# glove5.net
KiCad netlist of a schematic drawn in EAGLE
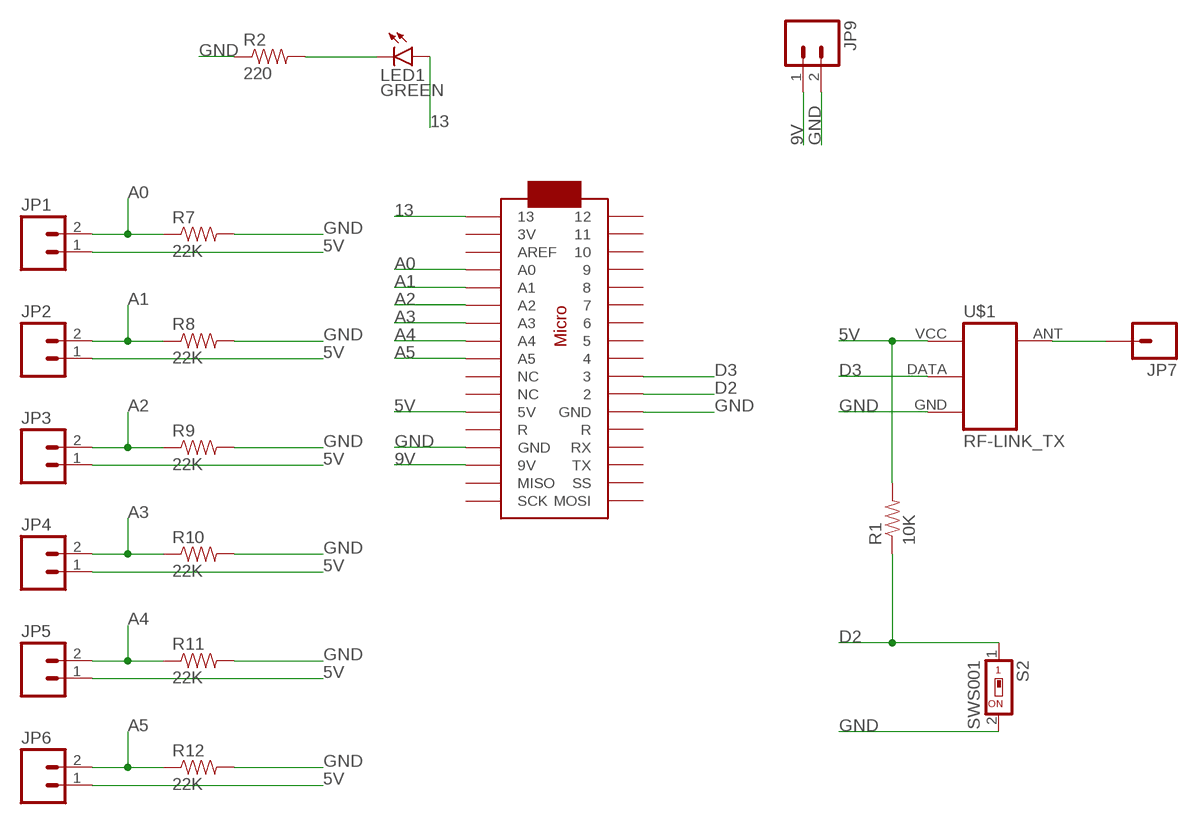
[diagram p0: schematic, sheet 1]

(export (version "E")
  (design (tool "Eeschema 10.0.6"))
  (components
    (comp (ref "JP1")
      (value "M02LOCK_LONGPADS")
      (footprint "eagle-import:1X02_LOCK_LONGPADS")
      (libsource (lib "eagle-import") (part "M02LOCK_LONGPADS"))
    )
    (comp (ref "JP2")
      (value "M02LOCK_LONGPADS")
      (footprint "eagle-import:1X02_LOCK_LONGPADS")
      (libsource (lib "eagle-import") (part "M02LOCK_LONGPADS"))
    )
    (comp (ref "JP3")
      (value "M02LOCK_LONGPADS")
      (footprint "eagle-import:1X02_LOCK_LONGPADS")
      (libsource (lib "eagle-import") (part "M02LOCK_LONGPADS"))
    )
    (comp (ref "JP4")
      (value "M02LOCK_LONGPADS")
      (footprint "eagle-import:1X02_LOCK_LONGPADS")
      (libsource (lib "eagle-import") (part "M02LOCK_LONGPADS"))
    )
    (comp (ref "JP5")
      (value "M02LOCK_LONGPADS")
      (footprint "eagle-import:1X02_LOCK_LONGPADS")
      (libsource (lib "eagle-import") (part "M02LOCK_LONGPADS"))
    )
    (comp (ref "JP6")
      (value "M02LOCK_LONGPADS")
      (footprint "eagle-import:1X02_LOCK_LONGPADS")
      (libsource (lib "eagle-import") (part "M02LOCK_LONGPADS"))
    )
    (comp (ref "JP7")
      (value "M01PTH_LONGPAD")
      (footprint "eagle-import:1X01_LONGPAD")
      (libsource (lib "eagle-import") (part "M01PTH_LONGPAD"))
    )
    (comp (ref "JP9")
      (value "M02LOCK_LONGPADS")
      (footprint "eagle-import:1X02_LOCK_LONGPADS")
      (libsource (lib "eagle-import") (part "M02LOCK_LONGPADS"))
    )
    (comp (ref "LED1")
      (value "GREEN")
      (footprint "eagle-import:FKIT-LED-1206")
      (libsource (lib "eagle-import") (part "LED-FKIT-1206"))
    )
    (comp (ref "R1")
      (value "10K")
      (footprint "eagle-import:1206")
      (libsource (lib "eagle-import") (part "RESISTOR1206"))
    )
    (comp (ref "R2")
      (value "220")
      (footprint "eagle-import:1206")
      (libsource (lib "eagle-import") (part "RESISTOR1206"))
    )
    (comp (ref "R7")
      (value "22K")
      (footprint "eagle-import:1206")
      (libsource (lib "eagle-import") (part "RESISTOR1206"))
    )
    (comp (ref "R8")
      (value "22K")
      (footprint "eagle-import:1206")
      (libsource (lib "eagle-import") (part "RESISTOR1206"))
    )
    (comp (ref "R9")
      (value "22K")
      (footprint "eagle-import:1206")
      (libsource (lib "eagle-import") (part "RESISTOR1206"))
    )
    (comp (ref "R10")
      (value "22K")
      (footprint "eagle-import:1206")
      (libsource (lib "eagle-import") (part "RESISTOR1206"))
    )
    (comp (ref "R11")
      (value "22K")
      (footprint "eagle-import:1206")
      (libsource (lib "eagle-import") (part "RESISTOR1206"))
    )
    (comp (ref "R12")
      (value "22K")
      (footprint "eagle-import:1206")
      (libsource (lib "eagle-import") (part "RESISTOR1206"))
    )
    (comp (ref "S2")
      (value "SWS001")
      (footprint "eagle-import:SMS-001")
      (libsource (lib "eagle-import") (part "SWS001"))
    )
    (comp (ref "U$1")
      (value "RF-LINK_TX")
      (footprint "eagle-import:RF-LINK_TX")
      (libsource (lib "eagle-import") (part "RF-LINK_TX"))
    )
    (comp (ref "U$3")
      (value "ARDUINOMICRO")
      (footprint "eagle-import:ARDUINOMICRO")
      (libsource (lib "eagle-import") (part "ARDUINOMICRO"))
    )
  )
  (nets
    (net (code "1") (name "/5V") (class "Default")
      (node (ref "JP1") (pin "1") (pinfunction "1_1") (pintype "passive"))
      (node (ref "JP2") (pin "1") (pinfunction "1_1") (pintype "passive"))
      (node (ref "JP3") (pin "1") (pinfunction "1_1") (pintype "passive"))
      (node (ref "JP4") (pin "1") (pinfunction "1_1") (pintype "passive"))
      (node (ref "JP5") (pin "1") (pinfunction "1_1") (pintype "passive"))
      (node (ref "JP6") (pin "1") (pinfunction "1_1") (pintype "passive"))
      (node (ref "R1") (pin "2") (pinfunction "2_2") (pintype "passive"))
      (node (ref "U$1") (pin "VCC") (pinfunction "+5V_VCC") (pintype "power_in"))
      (node (ref "U$3") (pin "P$23") (pinfunction "5V_P$23") (pintype "bidirectional"))
    )
    (net (code "2") (name "/9V") (class "Default")
      (node (ref "JP9") (pin "1") (pinfunction "1_1") (pintype "passive"))
      (node (ref "U$3") (pin "P$20") (pinfunction "9V_P$20") (pintype "bidirectional"))
    )
    (net (code "3") (name "/13") (class "Default")
      (node (ref "LED1") (pin "A") (pinfunction "A_A") (pintype "passive"))
      (node (ref "U$3") (pin "P$34") (pinfunction "13_P$34") (pintype "bidirectional"))
    )
    (net (code "4") (name "/A0") (class "Default")
      (node (ref "JP1") (pin "2") (pinfunction "2_2") (pintype "passive"))
      (node (ref "R7") (pin "1") (pinfunction "1_1") (pintype "passive"))
      (node (ref "U$3") (pin "P$31") (pinfunction "A0_P$31") (pintype "bidirectional"))
    )
    (net (code "5") (name "/A1") (class "Default")
      (node (ref "JP2") (pin "2") (pinfunction "2_2") (pintype "passive"))
      (node (ref "R8") (pin "1") (pinfunction "1_1") (pintype "passive"))
      (node (ref "U$3") (pin "P$30") (pinfunction "A1_P$30") (pintype "bidirectional"))
    )
    (net (code "6") (name "/A2") (class "Default")
      (node (ref "JP3") (pin "2") (pinfunction "2_2") (pintype "passive"))
      (node (ref "R9") (pin "1") (pinfunction "1_1") (pintype "passive"))
      (node (ref "U$3") (pin "P$29") (pinfunction "A2_P$29") (pintype "bidirectional"))
    )
    (net (code "7") (name "/A3") (class "Default")
      (node (ref "JP4") (pin "2") (pinfunction "2_2") (pintype "passive"))
      (node (ref "R10") (pin "1") (pinfunction "1_1") (pintype "passive"))
      (node (ref "U$3") (pin "P$28") (pinfunction "A3_P$28") (pintype "bidirectional"))
    )
    (net (code "8") (name "/A4") (class "Default")
      (node (ref "JP5") (pin "2") (pinfunction "2_2") (pintype "passive"))
      (node (ref "R11") (pin "1") (pinfunction "1_1") (pintype "passive"))
      (node (ref "U$3") (pin "P$27") (pinfunction "A4_P$27") (pintype "bidirectional"))
    )
    (net (code "9") (name "/A5") (class "Default")
      (node (ref "JP6") (pin "2") (pinfunction "2_2") (pintype "passive"))
      (node (ref "R12") (pin "1") (pinfunction "1_1") (pintype "passive"))
      (node (ref "U$3") (pin "P$26") (pinfunction "A5_P$26") (pintype "bidirectional"))
    )
    (net (code "10") (name "/D2") (class "Default")
      (node (ref "R1") (pin "1") (pinfunction "1_1") (pintype "passive"))
      (node (ref "S2") (pin "1") (pinfunction "1_1") (pintype "passive"))
      (node (ref "U$3") (pin "P$11") (pinfunction "2_P$11") (pintype "bidirectional"))
    )
    (net (code "11") (name "/D3") (class "Default")
      (node (ref "U$1") (pin "DATA") (pinfunction "DATA_DATA") (pintype "input"))
      (node (ref "U$3") (pin "P$10") (pinfunction "3_P$10") (pintype "bidirectional"))
    )
    (net (code "12") (name "/GND") (class "Default")
      (node (ref "JP9") (pin "2") (pinfunction "2_2") (pintype "passive"))
      (node (ref "R10") (pin "2") (pinfunction "2_2") (pintype "passive"))
      (node (ref "R11") (pin "2") (pinfunction "2_2") (pintype "passive"))
      (node (ref "R12") (pin "2") (pinfunction "2_2") (pintype "passive"))
      (node (ref "R2") (pin "1") (pinfunction "1_1") (pintype "passive"))
      (node (ref "R7") (pin "2") (pinfunction "2_2") (pintype "passive"))
      (node (ref "R8") (pin "2") (pinfunction "2_2") (pintype "passive"))
      (node (ref "R9") (pin "2") (pinfunction "2_2") (pintype "passive"))
      (node (ref "S2") (pin "2") (pinfunction "2_2") (pintype "passive"))
      (node (ref "U$1") (pin "GND") (pinfunction "GND_GND") (pintype "power_in"))
      (node (ref "U$3") (pin "P$12") (pinfunction "GND_P$12") (pintype "bidirectional"))
      (node (ref "U$3") (pin "P$21") (pinfunction "GND_P$21") (pintype "bidirectional"))
    )
    (net (code "13") (name "Net-(JP7-Pad1)") (class "Default")
      (node (ref "JP7") (pin "1") (pinfunction "1_1") (pintype "passive"))
      (node (ref "U$1") (pin "ANT") (pinfunction "ANT_ANT") (pintype "passive"))
    )
    (net (code "14") (name "Net-(LED1-PadC)") (class "Default")
      (node (ref "LED1") (pin "C") (pinfunction "C_C") (pintype "passive"))
      (node (ref "R2") (pin "2") (pinfunction "2_2") (pintype "passive"))
    )
    (net (code "15") (name "unconnected-(U$3-3V-PadP$33)") (class "Default")
      (node (ref "U$3") (pin "P$33") (pinfunction "3V_P$33") (pintype "bidirectional"))
    )
    (net (code "16") (name "unconnected-(U$3-4-PadP$9)") (class "Default")
      (node (ref "U$3") (pin "P$9") (pinfunction "4_P$9") (pintype "bidirectional"))
    )
    (net (code "17") (name "unconnected-(U$3-5-PadP$8)") (class "Default")
      (node (ref "U$3") (pin "P$8") (pinfunction "5_P$8") (pintype "bidirectional"))
    )
    (net (code "18") (name "unconnected-(U$3-6-PadP$7)") (class "Default")
      (node (ref "U$3") (pin "P$7") (pinfunction "6_P$7") (pintype "bidirectional"))
    )
    (net (code "19") (name "unconnected-(U$3-7-PadP$6)") (class "Default")
      (node (ref "U$3") (pin "P$6") (pinfunction "7_P$6") (pintype "bidirectional"))
    )
    (net (code "20") (name "unconnected-(U$3-8-PadP$5)") (class "Default")
      (node (ref "U$3") (pin "P$5") (pinfunction "8_P$5") (pintype "bidirectional"))
    )
    (net (code "21") (name "unconnected-(U$3-9-PadP$4)") (class "Default")
      (node (ref "U$3") (pin "P$4") (pinfunction "9_P$4") (pintype "bidirectional"))
    )
    (net (code "22") (name "unconnected-(U$3-10-PadP$3)") (class "Default")
      (node (ref "U$3") (pin "P$3") (pinfunction "10_P$3") (pintype "bidirectional"))
    )
    (net (code "23") (name "unconnected-(U$3-11-PadP$2)") (class "Default")
      (node (ref "U$3") (pin "P$2") (pinfunction "11_P$2") (pintype "bidirectional"))
    )
    (net (code "24") (name "unconnected-(U$3-12-PadP$1)") (class "Default")
      (node (ref "U$3") (pin "P$1") (pinfunction "12_P$1") (pintype "bidirectional"))
    )
    (net (code "25") (name "unconnected-(U$3-AREF-PadP$32)") (class "Default")
      (node (ref "U$3") (pin "P$32") (pinfunction "AREF_P$32") (pintype "bidirectional"))
    )
    (net (code "26") (name "unconnected-(U$3-MISO-PadP$19)") (class "Default")
      (node (ref "U$3") (pin "P$19") (pinfunction "MISO_P$19") (pintype "bidirectional"))
    )
    (net (code "27") (name "unconnected-(U$3-MOSI-PadP$17)") (class "Default")
      (node (ref "U$3") (pin "P$17") (pinfunction "MOSI_P$17") (pintype "bidirectional"))
    )
    (net (code "28") (name "unconnected-(U$3-NC-PadP$24)") (class "Default")
      (node (ref "U$3") (pin "P$24") (pinfunction "NC_P$24") (pintype "bidirectional"))
    )
    (net (code "29") (name "unconnected-(U$3-NC-PadP$25)") (class "Default")
      (node (ref "U$3") (pin "P$25") (pinfunction "NC_P$25") (pintype "bidirectional"))
    )
    (net (code "30") (name "unconnected-(U$3-R-PadP$13)") (class "Default")
      (node (ref "U$3") (pin "P$13") (pinfunction "R_P$13") (pintype "bidirectional"))
    )
    (net (code "31") (name "unconnected-(U$3-R-PadP$22)") (class "Default")
      (node (ref "U$3") (pin "P$22") (pinfunction "R_P$22") (pintype "bidirectional"))
    )
    (net (code "32") (name "unconnected-(U$3-RX-PadP$14)") (class "Default")
      (node (ref "U$3") (pin "P$14") (pinfunction "RX_P$14") (pintype "bidirectional"))
    )
    (net (code "33") (name "unconnected-(U$3-SCK-PadP$18)") (class "Default")
      (node (ref "U$3") (pin "P$18") (pinfunction "SCK_P$18") (pintype "bidirectional"))
    )
    (net (code "34") (name "unconnected-(U$3-SS-PadP$16)") (class "Default")
      (node (ref "U$3") (pin "P$16") (pinfunction "SS_P$16") (pintype "bidirectional"))
    )
    (net (code "35") (name "unconnected-(U$3-TX-PadP$15)") (class "Default")
      (node (ref "U$3") (pin "P$15") (pinfunction "TX_P$15") (pintype "bidirectional"))
    )
  )
)
